# OSO-SCAN-A1-00_Sensor_Candle_Concept.net
KiCad netlist of a schematic drawn in EAGLE
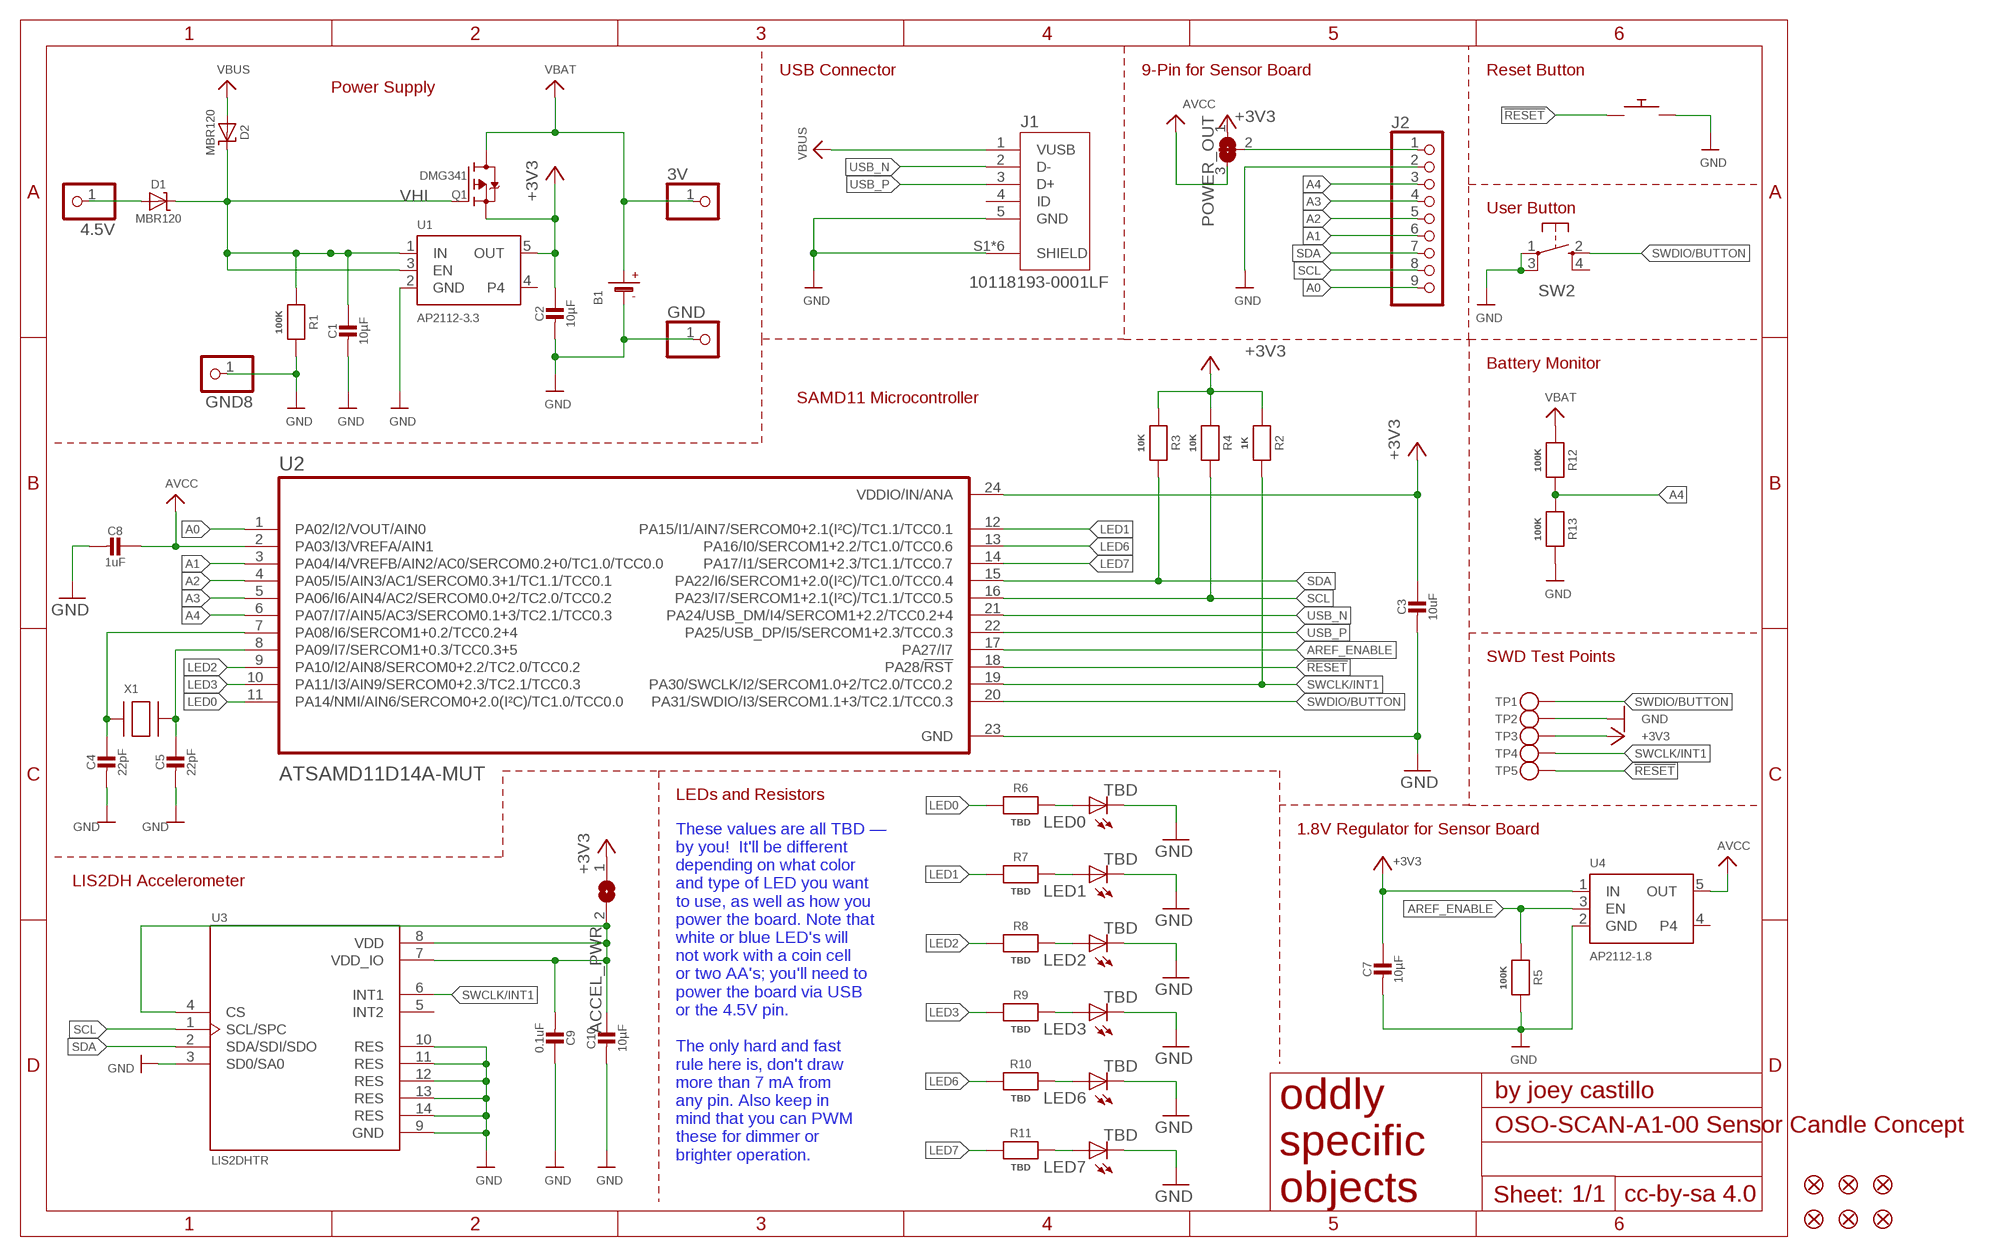
[diagram p0: schematic, sheet 1]

(export (version "E")
  (design (tool "Eeschema 10.0.6"))
  (components
    (comp (ref "3V")
      (value "PINHD-1X1")
      (footprint "eagle-import:1X01")
      (libsource (lib "eagle-import") (part "PINHD-1X1"))
    )
    (comp (ref "4.5V")
      (value "PINHD-1X1")
      (footprint "eagle-import:1X01")
      (libsource (lib "eagle-import") (part "PINHD-1X1"))
    )
    (comp (ref "ACCEL_PWR")
      (value "SOLDERJUMPERREFLOW_NOPASTE")
      (footprint "eagle-import:SOLDERJUMPER_REFLOW_NOPASTE")
      (libsource (lib "eagle-import") (part "SOLDERJUMPERREFLOW_NOPASTE"))
    )
    (comp (ref "B1")
      (value "BATTERY")
      (footprint "eagle-import:CR2032_SMT_BAT-HLD-BC-2003")
      (libsource (lib "eagle-import") (part "BATTERY"))
    )
    (comp (ref "C1")
      (value "10µF")
      (footprint "eagle-import:0805-NO")
      (libsource (lib "eagle-import") (part "CAP_CERAMIC0805-NOOUTLINE"))
    )
    (comp (ref "C2")
      (value "10µF")
      (footprint "eagle-import:0805-NO")
      (libsource (lib "eagle-import") (part "CAP_CERAMIC0805-NOOUTLINE"))
    )
    (comp (ref "C3")
      (value "10uF")
      (footprint "eagle-import:0805-NO")
      (libsource (lib "eagle-import") (part "CAP_CERAMIC0805-NOOUTLINE"))
    )
    (comp (ref "C4")
      (value "22pF")
      (footprint "eagle-import:0805-NO")
      (libsource (lib "eagle-import") (part "CAP_CERAMIC0805-NOOUTLINE"))
    )
    (comp (ref "C5")
      (value "22pF")
      (footprint "eagle-import:0805-NO")
      (libsource (lib "eagle-import") (part "CAP_CERAMIC0805-NOOUTLINE"))
    )
    (comp (ref "C7")
      (value "10µF")
      (footprint "eagle-import:0805-NO")
      (libsource (lib "eagle-import") (part "CAP_CERAMIC0805-NOOUTLINE"))
    )
    (comp (ref "C8")
      (value "1uF")
      (footprint "eagle-import:0805-NO")
      (libsource (lib "eagle-import") (part "CAP_CERAMIC0805-NOOUTLINE"))
    )
    (comp (ref "C9")
      (value "0.1uF")
      (footprint "eagle-import:0805-NO")
      (libsource (lib "eagle-import") (part "CAP_CERAMIC0805-NOOUTLINE"))
    )
    (comp (ref "C10")
      (value "10µF")
      (footprint "eagle-import:0805-NO")
      (libsource (lib "eagle-import") (part "CAP_CERAMIC0805-NOOUTLINE"))
    )
    (comp (ref "D1")
      (value "MBR120")
      (footprint "eagle-import:SOD-123")
      (libsource (lib "eagle-import") (part "DIODE-SCHOTTKYSOD-123"))
    )
    (comp (ref "D2")
      (value "MBR120")
      (footprint "eagle-import:SOD-123")
      (libsource (lib "eagle-import") (part "DIODE-SCHOTTKYSOD-123"))
    )
    (comp (ref "FID1")
      (value "FIDUCIAL_1MM")
      (footprint "eagle-import:FIDUCIAL_1MM")
      (libsource (lib "eagle-import") (part "FIDUCIAL_1MM"))
    )
    (comp (ref "FID2")
      (value "FIDUCIAL_1MM")
      (footprint "eagle-import:FIDUCIAL_1MM")
      (libsource (lib "eagle-import") (part "FIDUCIAL_1MM"))
    )
    (comp (ref "FID3")
      (value "FIDUCIAL_1MM")
      (footprint "eagle-import:FIDUCIAL_1MM")
      (libsource (lib "eagle-import") (part "FIDUCIAL_1MM"))
    )
    (comp (ref "FID4")
      (value "FIDUCIAL_1MM")
      (footprint "eagle-import:FIDUCIAL_1MM")
      (libsource (lib "eagle-import") (part "FIDUCIAL_1MM"))
    )
    (comp (ref "FID5")
      (value "FIDUCIAL_1MM")
      (footprint "eagle-import:FIDUCIAL_1MM")
      (libsource (lib "eagle-import") (part "FIDUCIAL_1MM"))
    )
    (comp (ref "FID6")
      (value "FIDUCIAL_1MM")
      (footprint "eagle-import:FIDUCIAL_1MM")
      (libsource (lib "eagle-import") (part "FIDUCIAL_1MM"))
    )
    (comp (ref "GND")
      (value "PINHD-1X1")
      (footprint "eagle-import:1X01")
      (libsource (lib "eagle-import") (part "PINHD-1X1"))
    )
    (comp (ref "GND8")
      (value "PINHD-1X1")
      (footprint "eagle-import:1X01")
      (libsource (lib "eagle-import") (part "PINHD-1X1"))
    )
    (comp (ref "J1")
      (value "10118193-0001LF")
      (footprint "eagle-import:FCI_10118193-0001LF")
      (fields (field (name "DIGI-KEY_PART_NUMBER") "609-4616-1-ND") (field (name "MF") "Amphenol ICC"))
      (libsource (lib "eagle-import") (part "10118193-0001LF"))
    )
    (comp (ref "J2")
      (value "HEADER-1X9_JSTSH")
      (footprint "eagle-import:JST_SH9")
      (libsource (lib "eagle-import") (part "HEADER-1X9_JSTSH"))
    )
    (comp (ref "LED0")
      (value "TBD")
      (footprint "eagle-import:CHIP-LED0805")
      (libsource (lib "eagle-import") (part "LEDCHIP-LED0805"))
    )
    (comp (ref "LED1")
      (value "TBD")
      (footprint "eagle-import:CHIP-LED0805")
      (libsource (lib "eagle-import") (part "LEDCHIP-LED0805"))
    )
    (comp (ref "LED2")
      (value "TBD")
      (footprint "eagle-import:CHIP-LED0805")
      (libsource (lib "eagle-import") (part "LEDCHIP-LED0805"))
    )
    (comp (ref "LED3")
      (value "TBD")
      (footprint "eagle-import:CHIP-LED0805")
      (libsource (lib "eagle-import") (part "LEDCHIP-LED0805"))
    )
    (comp (ref "LED6")
      (value "TBD")
      (footprint "eagle-import:CHIP-LED0805")
      (libsource (lib "eagle-import") (part "LEDCHIP-LED0805"))
    )
    (comp (ref "LED7")
      (value "TBD")
      (footprint "eagle-import:CHIP-LED0805")
      (libsource (lib "eagle-import") (part "LEDCHIP-LED0805"))
    )
    (comp (ref "POWER_OUT")
      (value "SOLDERJUMPER_2WAY")
      (footprint "eagle-import:SOLDERJUMPER_2WAY_OPEN_NOPASTE")
      (libsource (lib "eagle-import") (part "SOLDERJUMPER_2WAY"))
    )
    (comp (ref "Q1")
      (value "DMG341")
      (footprint "eagle-import:SOT23-R")
      (libsource (lib "eagle-import") (part "MOSFET-P"))
    )
    (comp (ref "R1")
      (value "100K")
      (footprint "eagle-import:0805-NO")
      (libsource (lib "eagle-import") (part "RESISTOR0805_NOOUTLINE"))
    )
    (comp (ref "R2")
      (value "1K")
      (footprint "eagle-import:0805-NO")
      (libsource (lib "eagle-import") (part "RESISTOR0805_NOOUTLINE"))
    )
    (comp (ref "R3")
      (value "10K")
      (footprint "eagle-import:0805-NO")
      (libsource (lib "eagle-import") (part "RESISTOR0805_NOOUTLINE"))
    )
    (comp (ref "R4")
      (value "10K")
      (footprint "eagle-import:0805-NO")
      (libsource (lib "eagle-import") (part "RESISTOR0805_NOOUTLINE"))
    )
    (comp (ref "R5")
      (value "100K")
      (footprint "eagle-import:0805-NO")
      (libsource (lib "eagle-import") (part "RESISTOR0805_NOOUTLINE"))
    )
    (comp (ref "R6")
      (value "TBD")
      (footprint "eagle-import:0805-NO")
      (libsource (lib "eagle-import") (part "RESISTOR0805_NOOUTLINE"))
    )
    (comp (ref "R7")
      (value "TBD")
      (footprint "eagle-import:0805-NO")
      (libsource (lib "eagle-import") (part "RESISTOR0805_NOOUTLINE"))
    )
    (comp (ref "R8")
      (value "TBD")
      (footprint "eagle-import:0805-NO")
      (libsource (lib "eagle-import") (part "RESISTOR0805_NOOUTLINE"))
    )
    (comp (ref "R9")
      (value "TBD")
      (footprint "eagle-import:0805-NO")
      (libsource (lib "eagle-import") (part "RESISTOR0805_NOOUTLINE"))
    )
    (comp (ref "R10")
      (value "TBD")
      (footprint "eagle-import:0805-NO")
      (libsource (lib "eagle-import") (part "RESISTOR0805_NOOUTLINE"))
    )
    (comp (ref "R11")
      (value "TBD")
      (footprint "eagle-import:0805-NO")
      (libsource (lib "eagle-import") (part "RESISTOR0805_NOOUTLINE"))
    )
    (comp (ref "R12")
      (value "100K")
      (footprint "eagle-import:0805-NO")
      (libsource (lib "eagle-import") (part "RESISTOR0805_NOOUTLINE"))
    )
    (comp (ref "R13")
      (value "100K")
      (footprint "eagle-import:0805-NO")
      (libsource (lib "eagle-import") (part "RESISTOR0805_NOOUTLINE"))
    )
    (comp (ref "RESET")
      (value "SWITCH_PUSHBUTTONC&K_KSS")
      (footprint "eagle-import:BTN_CK_KSS")
      (libsource (lib "eagle-import") (part "SWITCH_PUSHBUTTONC&K_KSS"))
    )
    (comp (ref "SW2")
      (value "SPST_TACT-KMR2")
      (footprint "eagle-import:KMR2")
      (libsource (lib "eagle-import") (part "SPST_TACT-KMR2"))
    )
    (comp (ref "TP1")
      (value "TESTPOINTROUND2MMNO")
      (footprint "eagle-import:TESTPOINT_ROUND_2MM_NO")
      (libsource (lib "eagle-import") (part "TESTPOINTROUND2MMNO"))
    )
    (comp (ref "TP2")
      (value "TESTPOINTROUND2MMNO")
      (footprint "eagle-import:TESTPOINT_ROUND_2MM_NO")
      (libsource (lib "eagle-import") (part "TESTPOINTROUND2MMNO"))
    )
    (comp (ref "TP3")
      (value "TESTPOINTROUND2MMNO")
      (footprint "eagle-import:TESTPOINT_ROUND_2MM_NO")
      (libsource (lib "eagle-import") (part "TESTPOINTROUND2MMNO"))
    )
    (comp (ref "TP4")
      (value "TESTPOINTROUND2MMNO")
      (footprint "eagle-import:TESTPOINT_ROUND_2MM_NO")
      (libsource (lib "eagle-import") (part "TESTPOINTROUND2MMNO"))
    )
    (comp (ref "TP5")
      (value "TESTPOINTROUND2MMNO")
      (footprint "eagle-import:TESTPOINT_ROUND_2MM_NO")
      (libsource (lib "eagle-import") (part "TESTPOINTROUND2MMNO"))
    )
    (comp (ref "U1")
      (value "AP2112-3.3")
      (footprint "eagle-import:SOT23-5")
      (libsource (lib "eagle-import") (part "VREG_SOT23-5"))
    )
    (comp (ref "U2")
      (value "ATSAMD11D14A-MUT")
      (footprint "eagle-import:QFN50P400X400X90-25N")
      (fields (field (name "MF") "Microchip"))
      (libsource (lib "eagle-import") (part "ATSAMD11D14A-MUT"))
    )
    (comp (ref "U3")
      (value "LIS2DHTR")
      (footprint "eagle-import:PQFN35P200X200X100-14N")
      (fields (field (name "DIGI-KEY_PART_NUMBER") "497-13795-1-ND") (field (name "MF") "STMicroelectronics"))
      (libsource (lib "eagle-import") (part "LIS2DHTR"))
    )
    (comp (ref "U4")
      (value "AP2112-1.8")
      (footprint "eagle-import:SOT23-5")
      (libsource (lib "eagle-import") (part "VREG_SOT23-5"))
    )
    (comp (ref "X1")
      (value "XTAL-3.2X1.5")
      (footprint "eagle-import:XTAL3215")
      (libsource (lib "eagle-import") (part "XTAL-3.2X1.5"))
    )
  )
  (nets
    (net (code "1") (name "+3V3") (class "Default")
      (node (ref "ACCEL_PWR") (pin "1") (pinfunction "1_1") (pintype "passive"))
      (node (ref "C2") (pin "1") (pinfunction "1_1") (pintype "passive"))
      (node (ref "C3") (pin "1") (pinfunction "1_1") (pintype "passive"))
      (node (ref "C7") (pin "1") (pinfunction "1_1") (pintype "passive"))
      (node (ref "POWER_OUT") (pin "1") (pinfunction "1_1") (pintype "passive"))
      (node (ref "Q1") (pin "2") (pinfunction "S_2") (pintype "passive"))
      (node (ref "R2") (pin "1") (pinfunction "1_1") (pintype "passive"))
      (node (ref "R3") (pin "1") (pinfunction "1_1") (pintype "passive"))
      (node (ref "R4") (pin "1") (pinfunction "1_1") (pintype "passive"))
      (node (ref "TP3") (pin "P$1") (pinfunction "P$1_P$1") (pintype "bidirectional"))
      (node (ref "U1") (pin "5") (pinfunction "OUT_5") (pintype "power_in"))
      (node (ref "U2") (pin "24") (pinfunction "VDDIO/IN/ANA_24") (pintype "power_in"))
      (node (ref "U4") (pin "1") (pinfunction "IN_1") (pintype "power_in"))
    )
    (net (code "2") (name "/VHI") (class "Default")
      (node (ref "C1") (pin "1") (pinfunction "1_1") (pintype "passive"))
      (node (ref "D1") (pin "C") (pinfunction "C_C") (pintype "passive"))
      (node (ref "D2") (pin "C") (pinfunction "C_C") (pintype "passive"))
      (node (ref "Q1") (pin "1") (pinfunction "G_1") (pintype "passive"))
      (node (ref "R1") (pin "1") (pinfunction "1_1") (pintype "passive"))
      (node (ref "U1") (pin "1") (pinfunction "IN_1") (pintype "power_in"))
      (node (ref "U1") (pin "3") (pinfunction "EN_3") (pintype "input"))
    )
    (net (code "3") (name "/~{RESET}") (class "Default")
      (node (ref "RESET") (pin "P$1") (pinfunction "P$1_P$1") (pintype "passive"))
      (node (ref "TP5") (pin "P$1") (pinfunction "P$1_P$1") (pintype "bidirectional"))
      (node (ref "U2") (pin "18") (pinfunction "PA28/~{RST}_18") (pintype "bidirectional"))
    )
    (net (code "4") (name "A0") (class "Default")
      (node (ref "J2") (pin "9") (pinfunction "9_9") (pintype "passive"))
      (node (ref "U2") (pin "1") (pinfunction "PA02/I2/VOUT/AIN0_1") (pintype "bidirectional"))
    )
    (net (code "5") (name "A1") (class "Default")
      (node (ref "J2") (pin "6") (pinfunction "6_6") (pintype "passive"))
      (node (ref "U2") (pin "3") (pinfunction "PA04/I4/VREFB/AIN2/AC0/SERCOM0.2+0/TC1.0/TCC0.0_3") (pintype "bidirectional"))
    )
    (net (code "6") (name "A2") (class "Default")
      (node (ref "J2") (pin "5") (pinfunction "5_5") (pintype "passive"))
      (node (ref "U2") (pin "4") (pinfunction "PA05/I5/AIN3/AC1/SERCOM0.3+1/TC1.1/TCC0.1_4") (pintype "bidirectional"))
    )
    (net (code "7") (name "A3") (class "Default")
      (node (ref "J2") (pin "4") (pinfunction "4_4") (pintype "passive"))
      (node (ref "U2") (pin "5") (pinfunction "PA06/I6/AIN4/AC2/SERCOM0.0+2/TC2.0/TCC0.2_5") (pintype "bidirectional"))
    )
    (net (code "8") (name "A4") (class "Default")
      (node (ref "J2") (pin "3") (pinfunction "3_3") (pintype "passive"))
      (node (ref "R12") (pin "2") (pinfunction "2_2") (pintype "passive"))
      (node (ref "R13") (pin "1") (pinfunction "1_1") (pintype "passive"))
      (node (ref "U2") (pin "6") (pinfunction "PA07/I7/AIN5/AC3/SERCOM0.1+3/TC2.1/TCC0.3_6") (pintype "bidirectional"))
    )
    (net (code "9") (name "AREF_ENABLE") (class "Default")
      (node (ref "R5") (pin "1") (pinfunction "1_1") (pintype "passive"))
      (node (ref "U2") (pin "17") (pinfunction "PA27/I7_17") (pintype "bidirectional"))
      (node (ref "U4") (pin "3") (pinfunction "EN_3") (pintype "input"))
    )
    (net (code "10") (name "AVCC") (class "Default")
      (node (ref "C8") (pin "1") (pinfunction "1_1") (pintype "passive"))
      (node (ref "POWER_OUT") (pin "3") (pinfunction "3_3") (pintype "passive"))
      (node (ref "U2") (pin "2") (pinfunction "PA03/I3/VREFA/AIN1_2") (pintype "bidirectional"))
      (node (ref "U4") (pin "5") (pinfunction "OUT_5") (pintype "power_in"))
    )
    (net (code "11") (name "GND") (class "Default")
      (node (ref "B1") (pin "-") (pinfunction "-_-") (pintype "passive"))
      (node (ref "C1") (pin "2") (pinfunction "2_2") (pintype "passive"))
      (node (ref "C10") (pin "2") (pinfunction "2_2") (pintype "passive"))
      (node (ref "C2") (pin "2") (pinfunction "2_2") (pintype "passive"))
      (node (ref "C3") (pin "2") (pinfunction "2_2") (pintype "passive"))
      (node (ref "C4") (pin "2") (pinfunction "2_2") (pintype "passive"))
      (node (ref "C5") (pin "2") (pinfunction "2_2") (pintype "passive"))
      (node (ref "C7") (pin "2") (pinfunction "2_2") (pintype "passive"))
      (node (ref "C8") (pin "2") (pinfunction "2_2") (pintype "passive"))
      (node (ref "C9") (pin "1") (pinfunction "1_1") (pintype "passive"))
      (node (ref "GND") (pin "1") (pinfunction "1_1") (pintype "passive"))
      (node (ref "GND8") (pin "1") (pinfunction "1_1") (pintype "passive"))
      (node (ref "J1") (pin "5") (pinfunction "GND_5") (pintype "passive"))
      (node (ref "J1") (pin "S1") (pinfunction "SHIELD_S1") (pintype "passive"))
      (node (ref "J1") (pin "S2") (pinfunction "SHIELD_S2") (pintype "passive"))
      (node (ref "J1") (pin "S3") (pinfunction "SHIELD_S3") (pintype "passive"))
      (node (ref "J1") (pin "S4") (pinfunction "SHIELD_S4") (pintype "passive"))
      (node (ref "J1") (pin "S5") (pinfunction "SHIELD_S5") (pintype "passive"))
      (node (ref "J1") (pin "S6") (pinfunction "SHIELD_S6") (pintype "passive"))
      (node (ref "J2") (pin "2") (pinfunction "2_2") (pintype "passive"))
      (node (ref "LED0") (pin "C") (pinfunction "C_C") (pintype "passive"))
      (node (ref "LED1") (pin "C") (pinfunction "C_C") (pintype "passive"))
      (node (ref "LED2") (pin "C") (pinfunction "C_C") (pintype "passive"))
      (node (ref "LED3") (pin "C") (pinfunction "C_C") (pintype "passive"))
      (node (ref "LED6") (pin "C") (pinfunction "C_C") (pintype "passive"))
      (node (ref "LED7") (pin "C") (pinfunction "C_C") (pintype "passive"))
      (node (ref "R1") (pin "2") (pinfunction "2_2") (pintype "passive"))
      (node (ref "R13") (pin "2") (pinfunction "2_2") (pintype "passive"))
      (node (ref "R5") (pin "2") (pinfunction "2_2") (pintype "passive"))
      (node (ref "RESET") (pin "P$2") (pinfunction "P$2_P$2") (pintype "passive"))
      (node (ref "SW2") (pin "1") (pinfunction "P_1") (pintype "passive"))
      (node (ref "SW2") (pin "3") (pinfunction "P1_3") (pintype "passive"))
      (node (ref "TP2") (pin "P$1") (pinfunction "P$1_P$1") (pintype "bidirectional"))
      (node (ref "U1") (pin "2") (pinfunction "GND_2") (pintype "power_in"))
      (node (ref "U2") (pin "23") (pinfunction "GND_23") (pintype "power_in"))
      (node (ref "U3") (pin "10") (pinfunction "RES_10") (pintype "power_in"))
      (node (ref "U3") (pin "11") (pinfunction "RES_11") (pintype "power_in"))
      (node (ref "U3") (pin "12") (pinfunction "RES_12") (pintype "power_in"))
      (node (ref "U3") (pin "13") (pinfunction "RES_13") (pintype "power_in"))
      (node (ref "U3") (pin "14") (pinfunction "RES_14") (pintype "power_in"))
      (node (ref "U3") (pin "3") (pinfunction "SD0/SA0_3") (pintype "output"))
      (node (ref "U3") (pin "9") (pinfunction "GND_9") (pintype "power_in"))
      (node (ref "U4") (pin "2") (pinfunction "GND_2") (pintype "power_in"))
    )
    (net (code "12") (name "LED0") (class "Default")
      (node (ref "R6") (pin "1") (pinfunction "1_1") (pintype "passive"))
      (node (ref "U2") (pin "11") (pinfunction "PA14/NMI/AIN6/SERCOM0+2.0(I²C)/TC1.0/TCC0.0_11") (pintype "bidirectional"))
    )
    (net (code "13") (name "LED1") (class "Default")
      (node (ref "R7") (pin "1") (pinfunction "1_1") (pintype "passive"))
      (node (ref "U2") (pin "12") (pinfunction "PA15/I1/AIN7/SERCOM0+2.1(I²C)/TC1.1/TCC0.1_12") (pintype "bidirectional"))
    )
    (net (code "14") (name "LED2") (class "Default")
      (node (ref "R8") (pin "1") (pinfunction "1_1") (pintype "passive"))
      (node (ref "U2") (pin "9") (pinfunction "PA10/I2/AIN8/SERCOM0+2.2/TC2.0/TCC0.2_9") (pintype "bidirectional"))
    )
    (net (code "15") (name "LED3") (class "Default")
      (node (ref "R9") (pin "1") (pinfunction "1_1") (pintype "passive"))
      (node (ref "U2") (pin "10") (pinfunction "PA11/I3/AIN9/SERCOM0+2.3/TC2.1/TCC0.3_10") (pintype "bidirectional"))
    )
    (net (code "16") (name "LED6") (class "Default")
      (node (ref "R10") (pin "1") (pinfunction "1_1") (pintype "passive"))
      (node (ref "U2") (pin "13") (pinfunction "PA16/I0/SERCOM1+2.2/TC1.0/TCC0.6_13") (pintype "bidirectional"))
    )
    (net (code "17") (name "LED7") (class "Default")
      (node (ref "R11") (pin "1") (pinfunction "1_1") (pintype "passive"))
      (node (ref "U2") (pin "14") (pinfunction "PA17/I1/SERCOM1+2.3/TC1.1/TCC0.7_14") (pintype "bidirectional"))
    )
    (net (code "18") (name "Net-(4.5V-Pad1)") (class "Default")
      (node (ref "4.5V") (pin "1") (pinfunction "1_1") (pintype "passive"))
      (node (ref "D1") (pin "A") (pinfunction "A_A") (pintype "passive"))
    )
    (net (code "19") (name "Net-(J2-Pad1)") (class "Default")
      (node (ref "J2") (pin "1") (pinfunction "1_1") (pintype "passive"))
      (node (ref "POWER_OUT") (pin "2") (pinfunction "2_2") (pintype "passive"))
    )
    (net (code "20") (name "Net-(LED0-PadA)") (class "Default")
      (node (ref "LED0") (pin "A") (pinfunction "A_A") (pintype "passive"))
      (node (ref "R6") (pin "2") (pinfunction "2_2") (pintype "passive"))
    )
    (net (code "21") (name "Net-(LED1-PadA)") (class "Default")
      (node (ref "LED1") (pin "A") (pinfunction "A_A") (pintype "passive"))
      (node (ref "R7") (pin "2") (pinfunction "2_2") (pintype "passive"))
    )
    (net (code "22") (name "Net-(LED2-PadA)") (class "Default")
      (node (ref "LED2") (pin "A") (pinfunction "A_A") (pintype "passive"))
      (node (ref "R8") (pin "2") (pinfunction "2_2") (pintype "passive"))
    )
    (net (code "23") (name "Net-(LED3-PadA)") (class "Default")
      (node (ref "LED3") (pin "A") (pinfunction "A_A") (pintype "passive"))
      (node (ref "R9") (pin "2") (pinfunction "2_2") (pintype "passive"))
    )
    (net (code "24") (name "Net-(LED6-PadA)") (class "Default")
      (node (ref "LED6") (pin "A") (pinfunction "A_A") (pintype "passive"))
      (node (ref "R10") (pin "2") (pinfunction "2_2") (pintype "passive"))
    )
    (net (code "25") (name "Net-(LED7-PadA)") (class "Default")
      (node (ref "LED7") (pin "A") (pinfunction "A_A") (pintype "passive"))
      (node (ref "R11") (pin "2") (pinfunction "2_2") (pintype "passive"))
    )
    (net (code "26") (name "Net-(U2-PA08{slash}I6{slash}SERCOM1+0.2{slash}TCC0.2+4)") (class "Default")
      (node (ref "C4") (pin "1") (pinfunction "1_1") (pintype "passive"))
      (node (ref "U2") (pin "7") (pinfunction "PA08/I6/SERCOM1+0.2/TCC0.2+4_7") (pintype "bidirectional"))
      (node (ref "X1") (pin "P$1") (pinfunction "P$1_P$1") (pintype "bidirectional"))
    )
    (net (code "27") (name "Net-(U2-PA09{slash}I7{slash}SERCOM1+0.3{slash}TCC0.3+5)") (class "Default")
      (node (ref "C5") (pin "1") (pinfunction "1_1") (pintype "passive"))
      (node (ref "U2") (pin "8") (pinfunction "PA09/I7/SERCOM1+0.3/TCC0.3+5_8") (pintype "bidirectional"))
      (node (ref "X1") (pin "P$2") (pinfunction "P$2_P$2") (pintype "bidirectional"))
    )
    (net (code "28") (name "Net-(U3-CS)") (class "Default")
      (node (ref "ACCEL_PWR") (pin "2") (pinfunction "2_2") (pintype "passive"))
      (node (ref "C10") (pin "1") (pinfunction "1_1") (pintype "passive"))
      (node (ref "C9") (pin "2") (pinfunction "2_2") (pintype "passive"))
      (node (ref "U3") (pin "4") (pinfunction "CS_4") (pintype "input"))
      (node (ref "U3") (pin "7") (pinfunction "VDD_IO_7") (pintype "power_in"))
      (node (ref "U3") (pin "8") (pinfunction "VDD_8") (pintype "power_in"))
    )
    (net (code "29") (name "SCL") (class "Default")
      (node (ref "J2") (pin "8") (pinfunction "8_8") (pintype "passive"))
      (node (ref "R4") (pin "2") (pinfunction "2_2") (pintype "passive"))
      (node (ref "U2") (pin "16") (pinfunction "PA23/I7/SERCOM1+2.1(I²C)/TC1.1/TCC0.5_16") (pintype "bidirectional"))
      (node (ref "U3") (pin "1") (pinfunction "SCL/SPC_1") (pintype "input"))
    )
    (net (code "30") (name "SDA") (class "Default")
      (node (ref "J2") (pin "7") (pinfunction "7_7") (pintype "passive"))
      (node (ref "R3") (pin "2") (pinfunction "2_2") (pintype "passive"))
      (node (ref "U2") (pin "15") (pinfunction "PA22/I6/SERCOM1+2.0(I²C)/TC1.0/TCC0.4_15") (pintype "bidirectional"))
      (node (ref "U3") (pin "2") (pinfunction "SDA/SDI/SDO_2") (pintype "bidirectional"))
    )
    (net (code "31") (name "SWCLK{slash}INT1") (class "Default")
      (node (ref "R2") (pin "2") (pinfunction "2_2") (pintype "passive"))
      (node (ref "TP4") (pin "P$1") (pinfunction "P$1_P$1") (pintype "bidirectional"))
      (node (ref "U2") (pin "19") (pinfunction "PA30/SWCLK/I2/SERCOM1.0+2/TC2.0/TCC0.2_19") (pintype "bidirectional"))
      (node (ref "U3") (pin "6") (pinfunction "INT1_6") (pintype "output"))
    )
    (net (code "32") (name "SWDIO{slash}BUTTON") (class "Default")
      (node (ref "SW2") (pin "2") (pinfunction "S_2") (pintype "passive"))
      (node (ref "TP1") (pin "P$1") (pinfunction "P$1_P$1") (pintype "bidirectional"))
      (node (ref "U2") (pin "20") (pinfunction "PA31/SWDIO/I3/SERCOM1.1+3/TC2.1/TCC0.3_20") (pintype "bidirectional"))
    )
    (net (code "33") (name "USB_N") (class "Default")
      (node (ref "J1") (pin "2") (pinfunction "D-_2") (pintype "passive"))
      (node (ref "U2") (pin "21") (pinfunction "PA24/USB_DM/I4/SERCOM1+2.2/TCC0.2+4_21") (pintype "bidirectional"))
    )
    (net (code "34") (name "USB_P") (class "Default")
      (node (ref "J1") (pin "3") (pinfunction "D+_3") (pintype "passive"))
      (node (ref "U2") (pin "22") (pinfunction "PA25/USB_DP/I5/SERCOM1+2.3/TCC0.3_22") (pintype "bidirectional"))
    )
    (net (code "35") (name "VBAT") (class "Default")
      (node (ref "3V") (pin "1") (pinfunction "1_1") (pintype "passive"))
      (node (ref "B1") (pin "+$1") (pinfunction "+_+$1") (pintype "passive"))
      (node (ref "B1") (pin "+$2") (pinfunction "+_+$2") (pintype "passive"))
      (node (ref "Q1") (pin "3") (pinfunction "D_3") (pintype "passive"))
      (node (ref "R12") (pin "1") (pinfunction "1_1") (pintype "passive"))
    )
    (net (code "36") (name "VBUS") (class "Default")
      (node (ref "D2") (pin "A") (pinfunction "A_A") (pintype "passive"))
      (node (ref "J1") (pin "1") (pinfunction "VUSB_1") (pintype "passive"))
    )
    (net (code "37") (name "unconnected-(J1-ID-Pad4)") (class "Default")
      (node (ref "J1") (pin "4") (pinfunction "ID_4") (pintype "passive"))
    )
    (net (code "38") (name "unconnected-(SW2-S1-Pad4)") (class "Default")
      (node (ref "SW2") (pin "4") (pinfunction "S1_4") (pintype "passive"))
    )
    (net (code "39") (name "unconnected-(U1-P4-Pad4)") (class "Default")
      (node (ref "U1") (pin "4") (pinfunction "P4_4") (pintype "bidirectional"))
    )
    (net (code "40") (name "unconnected-(U3-INT2-Pad5)") (class "Default")
      (node (ref "U3") (pin "5") (pinfunction "INT2_5") (pintype "output"))
    )
    (net (code "41") (name "unconnected-(U4-P4-Pad4)") (class "Default")
      (node (ref "U4") (pin "4") (pinfunction "P4_4") (pintype "bidirectional"))
    )
  )
)
